# PHOTODIODE.net
KiCad netlist of a schematic drawn in Altium Designer
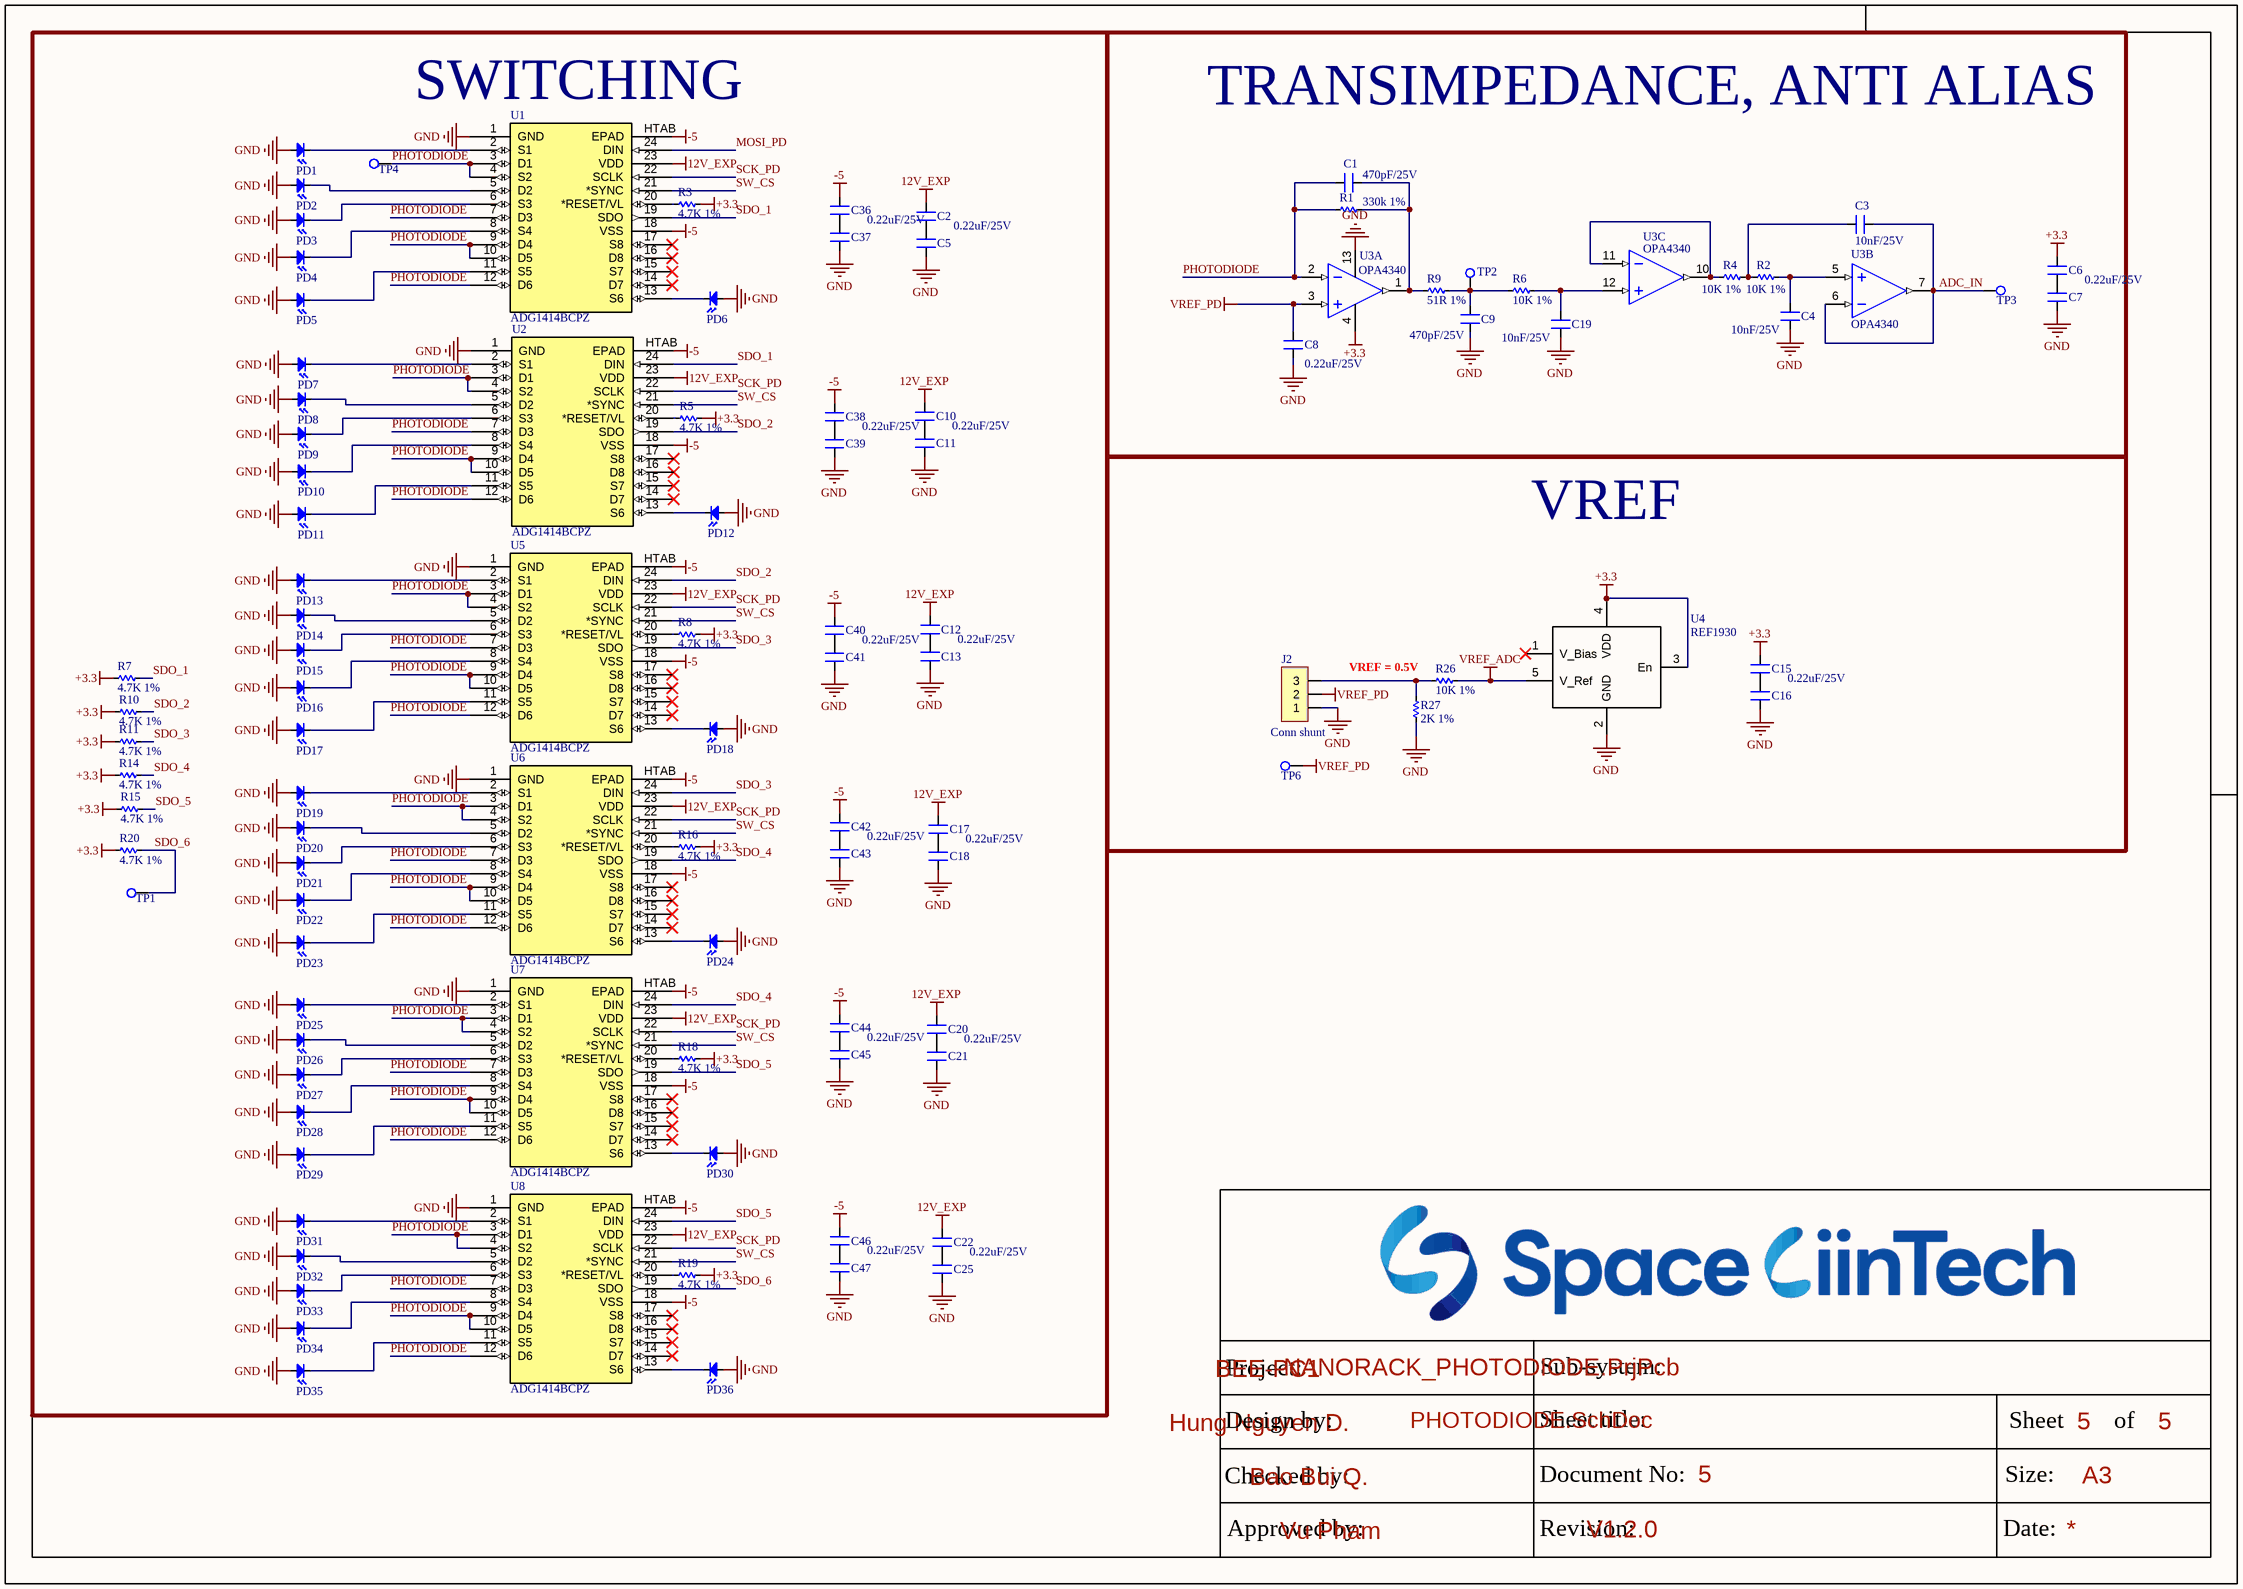
[diagram p0: PHOTODIODE.SchDoc]

(export (version "E")
  (design (tool "Eeschema 10.0.6"))
  (components
    (comp (ref "C1")
      (value "470pF/25V")
      (footprint "CN-SMD-0603")
      (description "0603")
      (libsource (lib "Capacitors") (part "CM"))
    )
    (comp (ref "C2")
      (value "0.22uF/25V")
      (footprint "CN-SMD-0603")
      (description "0603")
      (libsource (lib "Capacitors") (part "CM"))
    )
    (comp (ref "C3")
      (value "10nF/25V")
      (footprint "CN-SMD-0603")
      (description "0603")
      (libsource (lib "Capacitors") (part "CM"))
    )
    (comp (ref "C4")
      (value "10nF/25V")
      (footprint "CN-SMD-0603")
      (description "0603")
      (libsource (lib "Capacitors") (part "CM"))
    )
    (comp (ref "C5")
      (value "0.22uF/25V")
      (footprint "CN-SMD-0603")
      (description "0603")
      (libsource (lib "Capacitors") (part "CM"))
    )
    (comp (ref "C6")
      (value "0.22uF/25V")
      (footprint "CN-SMD-0603")
      (description "0603")
      (libsource (lib "Capacitors") (part "CM"))
    )
    (comp (ref "C7")
      (value "0.22uF/25V")
      (footprint "CN-SMD-0603")
      (description "0603")
      (libsource (lib "Capacitors") (part "CM"))
    )
    (comp (ref "C8")
      (value "0.22uF/25V")
      (footprint "CN-SMD-0603")
      (description "0603")
      (libsource (lib "Capacitors") (part "CM"))
    )
    (comp (ref "C9")
      (value "470pF/25V")
      (footprint "CN-SMD-0603")
      (description "0603")
      (libsource (lib "Capacitors") (part "CM"))
    )
    (comp (ref "C10")
      (value "0.22uF/25V")
      (footprint "CN-SMD-0603")
      (description "0603")
      (libsource (lib "Capacitors") (part "CM"))
    )
    (comp (ref "C11")
      (value "0.22uF/25V")
      (footprint "CN-SMD-0603")
      (description "0603")
      (libsource (lib "Capacitors") (part "CM"))
    )
    (comp (ref "C12")
      (value "0.22uF/25V")
      (footprint "CN-SMD-0603")
      (description "0603")
      (libsource (lib "Capacitors") (part "CM"))
    )
    (comp (ref "C13")
      (value "0.22uF/25V")
      (footprint "CN-SMD-0603")
      (description "0603")
      (libsource (lib "Capacitors") (part "CM"))
    )
    (comp (ref "C15")
      (value "0.22uF/25V")
      (footprint "CN-SMD-0603")
      (description "0603")
      (libsource (lib "Capacitors") (part "CM"))
    )
    (comp (ref "C16")
      (value "0.22uF/25V")
      (footprint "CN-SMD-0603")
      (description "0603")
      (libsource (lib "Capacitors") (part "CM"))
    )
    (comp (ref "C17")
      (value "0.22uF/25V")
      (footprint "CN-SMD-0603")
      (description "0603")
      (libsource (lib "Capacitors") (part "CM"))
    )
    (comp (ref "C18")
      (value "0.22uF/25V")
      (footprint "CN-SMD-0603")
      (description "0603")
      (libsource (lib "Capacitors") (part "CM"))
    )
    (comp (ref "C19")
      (value "10nF/25V")
      (footprint "CN-SMD-0603")
      (description "0603")
      (libsource (lib "Capacitors") (part "CM"))
    )
    (comp (ref "C20")
      (value "0.22uF/25V")
      (footprint "CN-SMD-0603")
      (description "0603")
      (libsource (lib "Capacitors") (part "CM"))
    )
    (comp (ref "C21")
      (value "0.22uF/25V")
      (footprint "CN-SMD-0603")
      (description "0603")
      (libsource (lib "Capacitors") (part "CM"))
    )
    (comp (ref "C22")
      (value "0.22uF/25V")
      (footprint "CN-SMD-0603")
      (description "0603")
      (libsource (lib "Capacitors") (part "CM"))
    )
    (comp (ref "C25")
      (value "0.22uF/25V")
      (footprint "CN-SMD-0603")
      (description "0603")
      (libsource (lib "Capacitors") (part "CM"))
    )
    (comp (ref "C36")
      (value "0.22uF/25V")
      (footprint "CN-SMD-0603")
      (description "0603")
      (libsource (lib "Capacitors") (part "CM"))
    )
    (comp (ref "C37")
      (value "0.22uF/25V")
      (footprint "CN-SMD-0603")
      (description "0603")
      (libsource (lib "Capacitors") (part "CM"))
    )
    (comp (ref "C38")
      (value "0.22uF/25V")
      (footprint "CN-SMD-0603")
      (description "0603")
      (libsource (lib "Capacitors") (part "CM"))
    )
    (comp (ref "C39")
      (value "0.22uF/25V")
      (footprint "CN-SMD-0603")
      (description "0603")
      (libsource (lib "Capacitors") (part "CM"))
    )
    (comp (ref "C40")
      (value "0.22uF/25V")
      (footprint "CN-SMD-0603")
      (description "0603")
      (libsource (lib "Capacitors") (part "CM"))
    )
    (comp (ref "C41")
      (value "0.22uF/25V")
      (footprint "CN-SMD-0603")
      (description "0603")
      (libsource (lib "Capacitors") (part "CM"))
    )
    (comp (ref "C42")
      (value "0.22uF/25V")
      (footprint "CN-SMD-0603")
      (description "0603")
      (libsource (lib "Capacitors") (part "CM"))
    )
    (comp (ref "C43")
      (value "0.22uF/25V")
      (footprint "CN-SMD-0603")
      (description "0603")
      (libsource (lib "Capacitors") (part "CM"))
    )
    (comp (ref "C44")
      (value "0.22uF/25V")
      (footprint "CN-SMD-0603")
      (description "0603")
      (libsource (lib "Capacitors") (part "CM"))
    )
    (comp (ref "C45")
      (value "0.22uF/25V")
      (footprint "CN-SMD-0603")
      (description "0603")
      (libsource (lib "Capacitors") (part "CM"))
    )
    (comp (ref "C46")
      (value "0.22uF/25V")
      (footprint "CN-SMD-0603")
      (description "0603")
      (libsource (lib "Capacitors") (part "CM"))
    )
    (comp (ref "C47")
      (value "0.22uF/25V")
      (footprint "CN-SMD-0603")
      (description "0603")
      (libsource (lib "Capacitors") (part "CM"))
    )
    (comp (ref "J2")
      (value "Conn shunt")
      (footprint "M50-3930342")
      (description "WR-PHD 2.54 mm Angled Socket Header")
      (fields
        (field (name "MANUFACTURER") "Würth Elektronik eiSos GmbH")
        (field (name "PARTNO") "613003143121")
        (field (name "CREATED BY") "Karrer Zheng")
      )
      (libsource (lib "Library") (part "JP3"))
    )
    (comp (ref "PD1")
      (value "Photodiode")
      (footprint "VEMD5080X01")
      (libsource (lib "Library_HUNG") (part "Photodiode"))
    )
    (comp (ref "PD2")
      (value "Photodiode")
      (footprint "VEMD5080X01")
      (libsource (lib "Library_HUNG") (part "Photodiode"))
    )
    (comp (ref "PD3")
      (value "Photodiode")
      (footprint "VEMD5080X01")
      (libsource (lib "Library_HUNG") (part "Photodiode"))
    )
    (comp (ref "PD4")
      (value "Photodiode")
      (footprint "VEMD5080X01")
      (libsource (lib "Library_HUNG") (part "Photodiode"))
    )
    (comp (ref "PD5")
      (value "Photodiode")
      (footprint "VEMD5080X01")
      (libsource (lib "Library_HUNG") (part "Photodiode"))
    )
    (comp (ref "PD6")
      (value "Photodiode")
      (footprint "VEMD5080X01")
      (libsource (lib "Library_HUNG") (part "Photodiode"))
    )
    (comp (ref "PD7")
      (value "Photodiode")
      (footprint "VEMD5080X01")
      (libsource (lib "Library_HUNG") (part "Photodiode"))
    )
    (comp (ref "PD8")
      (value "Photodiode")
      (footprint "VEMD5080X01")
      (libsource (lib "Library_HUNG") (part "Photodiode"))
    )
    (comp (ref "PD9")
      (value "Photodiode")
      (footprint "VEMD5080X01")
      (libsource (lib "Library_HUNG") (part "Photodiode"))
    )
    (comp (ref "PD10")
      (value "Photodiode")
      (footprint "VEMD5080X01")
      (libsource (lib "Library_HUNG") (part "Photodiode"))
    )
    (comp (ref "PD11")
      (value "Photodiode")
      (footprint "VEMD5080X01")
      (libsource (lib "Library_HUNG") (part "Photodiode"))
    )
    (comp (ref "PD12")
      (value "Photodiode")
      (footprint "VEMD5080X01")
      (libsource (lib "Library_HUNG") (part "Photodiode"))
    )
    (comp (ref "PD13")
      (value "Photodiode")
      (footprint "VEMD5080X01")
      (libsource (lib "Library_HUNG") (part "Photodiode"))
    )
    (comp (ref "PD14")
      (value "Photodiode")
      (footprint "VEMD5080X01")
      (libsource (lib "Library_HUNG") (part "Photodiode"))
    )
    (comp (ref "PD15")
      (value "Photodiode")
      (footprint "VEMD5080X01")
      (libsource (lib "Library_HUNG") (part "Photodiode"))
    )
    (comp (ref "PD16")
      (value "Photodiode")
      (footprint "VEMD5080X01")
      (libsource (lib "Library_HUNG") (part "Photodiode"))
    )
    (comp (ref "PD17")
      (value "Photodiode")
      (footprint "VEMD5080X01")
      (libsource (lib "Library_HUNG") (part "Photodiode"))
    )
    (comp (ref "PD18")
      (value "Photodiode")
      (footprint "VEMD5080X01")
      (libsource (lib "Library_HUNG") (part "Photodiode"))
    )
    (comp (ref "PD19")
      (value "Photodiode")
      (footprint "VEMD5080X01")
      (libsource (lib "Library_HUNG") (part "Photodiode"))
    )
    (comp (ref "PD20")
      (value "Photodiode")
      (footprint "VEMD5080X01")
      (libsource (lib "Library_HUNG") (part "Photodiode"))
    )
    (comp (ref "PD21")
      (value "Photodiode")
      (footprint "VEMD5080X01")
      (libsource (lib "Library_HUNG") (part "Photodiode"))
    )
    (comp (ref "PD22")
      (value "Photodiode")
      (footprint "VEMD5080X01")
      (libsource (lib "Library_HUNG") (part "Photodiode"))
    )
    (comp (ref "PD23")
      (value "Photodiode")
      (footprint "VEMD5080X01")
      (libsource (lib "Library_HUNG") (part "Photodiode"))
    )
    (comp (ref "PD24")
      (value "Photodiode")
      (footprint "VEMD5080X01")
      (libsource (lib "Library_HUNG") (part "Photodiode"))
    )
    (comp (ref "PD25")
      (value "Photodiode")
      (footprint "VEMD5080X01")
      (libsource (lib "Library_HUNG") (part "Photodiode"))
    )
    (comp (ref "PD26")
      (value "Photodiode")
      (footprint "VEMD5080X01")
      (libsource (lib "Library_HUNG") (part "Photodiode"))
    )
    (comp (ref "PD27")
      (value "Photodiode")
      (footprint "VEMD5080X01")
      (libsource (lib "Library_HUNG") (part "Photodiode"))
    )
    (comp (ref "PD28")
      (value "Photodiode")
      (footprint "VEMD5080X01")
      (libsource (lib "Library_HUNG") (part "Photodiode"))
    )
    (comp (ref "PD29")
      (value "Photodiode")
      (footprint "VEMD5080X01")
      (libsource (lib "Library_HUNG") (part "Photodiode"))
    )
    (comp (ref "PD30")
      (value "Photodiode")
      (footprint "VEMD5080X01")
      (libsource (lib "Library_HUNG") (part "Photodiode"))
    )
    (comp (ref "PD31")
      (value "Photodiode")
      (footprint "VEMD5080X01")
      (libsource (lib "Library_HUNG") (part "Photodiode"))
    )
    (comp (ref "PD32")
      (value "Photodiode")
      (footprint "VEMD5080X01")
      (libsource (lib "Library_HUNG") (part "Photodiode"))
    )
    (comp (ref "PD33")
      (value "Photodiode")
      (footprint "VEMD5080X01")
      (libsource (lib "Library_HUNG") (part "Photodiode"))
    )
    (comp (ref "PD34")
      (value "Photodiode")
      (footprint "VEMD5080X01")
      (libsource (lib "Library_HUNG") (part "Photodiode"))
    )
    (comp (ref "PD35")
      (value "Photodiode")
      (footprint "VEMD5080X01")
      (libsource (lib "Library_HUNG") (part "Photodiode"))
    )
    (comp (ref "PD36")
      (value "Photodiode")
      (footprint "VEMD5080X01")
      (libsource (lib "Library_HUNG") (part "Photodiode"))
    )
    (comp (ref "R1")
      (value "330k 1%")
      (footprint "RES-SMD-0603")
      (description "0603")
      (fields
        (field (name "MANUFACTURER") "Generic Components")
        (field (name "PUBLISHER") "Altium Hobart Technology Centre")
      )
      (libsource (lib "Library") (part "Res-SMD"))
    )
    (comp (ref "R2")
      (value "10K 1%")
      (footprint "RES-SMD-0603")
      (description "0603")
      (fields
        (field (name "MANUFACTURER") "Generic Components")
        (field (name "PUBLISHER") "Altium Hobart Technology Centre")
      )
      (libsource (lib "Library") (part "Res-SMD"))
    )
    (comp (ref "R3")
      (value "4.7K 1%")
      (footprint "RES-SMD-0603")
      (description "0603")
      (fields
        (field (name "MANUFACTURER") "Generic Components")
        (field (name "PUBLISHER") "Altium Hobart Technology Centre")
      )
      (libsource (lib "Library") (part "Res-SMD"))
    )
    (comp (ref "R4")
      (value "10K 1%")
      (footprint "RES-SMD-0603")
      (description "0603")
      (fields
        (field (name "MANUFACTURER") "Generic Components")
        (field (name "PUBLISHER") "Altium Hobart Technology Centre")
      )
      (libsource (lib "Library") (part "Res-SMD"))
    )
    (comp (ref "R5")
      (value "4.7K 1%")
      (footprint "RES-SMD-0603")
      (description "0603")
      (fields
        (field (name "MANUFACTURER") "Generic Components")
        (field (name "PUBLISHER") "Altium Hobart Technology Centre")
      )
      (libsource (lib "Library") (part "Res-SMD"))
    )
    (comp (ref "R6")
      (value "10K 1%")
      (footprint "RES-SMD-0603")
      (description "0603")
      (fields
        (field (name "MANUFACTURER") "Generic Components")
        (field (name "PUBLISHER") "Altium Hobart Technology Centre")
      )
      (libsource (lib "Library") (part "Res-SMD"))
    )
    (comp (ref "R7")
      (value "4.7K 1%")
      (footprint "RES-SMD-0603")
      (description "0603")
      (fields
        (field (name "MANUFACTURER") "Generic Components")
        (field (name "PUBLISHER") "Altium Hobart Technology Centre")
      )
      (libsource (lib "Library") (part "Res-SMD"))
    )
    (comp (ref "R8")
      (value "4.7K 1%")
      (footprint "RES-SMD-0603")
      (description "0603")
      (fields
        (field (name "MANUFACTURER") "Generic Components")
        (field (name "PUBLISHER") "Altium Hobart Technology Centre")
      )
      (libsource (lib "Library") (part "Res-SMD"))
    )
    (comp (ref "R9")
      (value "51R 1%")
      (footprint "RES-SMD-0603")
      (description "0603")
      (fields
        (field (name "MANUFACTURER") "Generic Components")
        (field (name "PUBLISHER") "Altium Hobart Technology Centre")
      )
      (libsource (lib "Library") (part "Res-SMD"))
    )
    (comp (ref "R10")
      (value "4.7K 1%")
      (footprint "RES-SMD-0603")
      (description "0603")
      (fields
        (field (name "MANUFACTURER") "Generic Components")
        (field (name "PUBLISHER") "Altium Hobart Technology Centre")
      )
      (libsource (lib "Library") (part "Res-SMD"))
    )
    (comp (ref "R11")
      (value "4.7K 1%")
      (footprint "RES-SMD-0603")
      (description "0603")
      (fields
        (field (name "MANUFACTURER") "Generic Components")
        (field (name "PUBLISHER") "Altium Hobart Technology Centre")
      )
      (libsource (lib "Library") (part "Res-SMD"))
    )
    (comp (ref "R14")
      (value "4.7K 1%")
      (footprint "RES-SMD-0603")
      (description "0603")
      (fields
        (field (name "MANUFACTURER") "Generic Components")
        (field (name "PUBLISHER") "Altium Hobart Technology Centre")
      )
      (libsource (lib "Library") (part "Res-SMD"))
    )
    (comp (ref "R15")
      (value "4.7K 1%")
      (footprint "RES-SMD-0603")
      (description "0603")
      (fields
        (field (name "MANUFACTURER") "Generic Components")
        (field (name "PUBLISHER") "Altium Hobart Technology Centre")
      )
      (libsource (lib "Library") (part "Res-SMD"))
    )
    (comp (ref "R16")
      (value "4.7K 1%")
      (footprint "RES-SMD-0603")
      (description "0603")
      (fields
        (field (name "MANUFACTURER") "Generic Components")
        (field (name "PUBLISHER") "Altium Hobart Technology Centre")
      )
      (libsource (lib "Library") (part "Res-SMD"))
    )
    (comp (ref "R18")
      (value "4.7K 1%")
      (footprint "RES-SMD-0603")
      (description "0603")
      (fields
        (field (name "MANUFACTURER") "Generic Components")
        (field (name "PUBLISHER") "Altium Hobart Technology Centre")
      )
      (libsource (lib "Library") (part "Res-SMD"))
    )
    (comp (ref "R19")
      (value "4.7K 1%")
      (footprint "RES-SMD-0603")
      (description "0603")
      (fields
        (field (name "MANUFACTURER") "Generic Components")
        (field (name "PUBLISHER") "Altium Hobart Technology Centre")
      )
      (libsource (lib "Library") (part "Res-SMD"))
    )
    (comp (ref "R20")
      (value "4.7K 1%")
      (footprint "RES-SMD-0603")
      (description "0603")
      (fields
        (field (name "MANUFACTURER") "Generic Components")
        (field (name "PUBLISHER") "Altium Hobart Technology Centre")
      )
      (libsource (lib "Library") (part "Res-SMD"))
    )
    (comp (ref "R26")
      (value "10K 1%")
      (footprint "RES-SMD-0603")
      (description "0603")
      (fields
        (field (name "MANUFACTURER") "Generic Components")
        (field (name "PUBLISHER") "Altium Hobart Technology Centre")
      )
      (libsource (lib "Library") (part "Res-SMD"))
    )
    (comp (ref "R27")
      (value "2K 1%")
      (footprint "RES-SMD-0603")
      (description "0603")
      (fields
        (field (name "MANUFACTURER") "Generic Components")
        (field (name "PUBLISHER") "Altium Hobart Technology Centre")
      )
      (libsource (lib "Library") (part "Res-SMD"))
    )
    (comp (ref "TP1")
      (value "Test_Point")
      (footprint "TESTPOINT")
      (libsource (lib "Library_HUNG") (part "Test_Point"))
    )
    (comp (ref "TP2")
      (value "Test_Point")
      (footprint "TESTPOINT")
      (libsource (lib "Library_HUNG") (part "Test_Point"))
    )
    (comp (ref "TP3")
      (value "Test_Point")
      (footprint "TESTPOINT")
      (libsource (lib "Library_HUNG") (part "Test_Point"))
    )
    (comp (ref "TP4")
      (value "Test_Point")
      (footprint "TESTPOINT")
      (libsource (lib "Library_HUNG") (part "Test_Point"))
    )
    (comp (ref "TP6")
      (value "Test_Point")
      (footprint "TESTPOINT")
      (libsource (lib "Library_HUNG") (part "Test_Point"))
    )
    (comp (ref "U1")
      (value "ADG1414BCPZ")
      (footprint "ADG1414BCPZ")
      (description "IC SW SPST-NOX8 11.5OHM 24LFCSP")
      (libsource (lib "Library_HUNG") (part "ADG1414"))
    )
    (comp (ref "U2")
      (value "ADG1414BCPZ")
      (footprint "ADG1414BCPZ")
      (description "IC SW SPST-NOX8 11.5OHM 24LFCSP")
      (libsource (lib "Library_HUNG") (part "ADG1414"))
    )
    (comp (ref "U3")
      (value "OPA4340")
      (footprint "SSOP16")
      (description "IC CMOS 4 CIRCUIT 16SSOP")
      (libsource (lib "Library") (part "OPA4340"))
    )
    (comp (ref "U4")
      (value "REF1930")
      (footprint "SOT23-5")
      (description "REF1941AIDDCT")
      (libsource (lib "Library") (part "REF19xx"))
    )
    (comp (ref "U5")
      (value "ADG1414BCPZ")
      (footprint "ADG1414BCPZ")
      (description "IC SW SPST-NOX8 11.5OHM 24LFCSP")
      (libsource (lib "Library_HUNG") (part "ADG1414"))
    )
    (comp (ref "U6")
      (value "ADG1414BCPZ")
      (footprint "ADG1414BCPZ")
      (description "IC SW SPST-NOX8 11.5OHM 24LFCSP")
      (libsource (lib "Library_HUNG") (part "ADG1414"))
    )
    (comp (ref "U7")
      (value "ADG1414BCPZ")
      (footprint "ADG1414BCPZ")
      (description "IC SW SPST-NOX8 11.5OHM 24LFCSP")
      (libsource (lib "Library_HUNG") (part "ADG1414"))
    )
    (comp (ref "U8")
      (value "ADG1414BCPZ")
      (footprint "ADG1414BCPZ")
      (description "IC SW SPST-NOX8 11.5OHM 24LFCSP")
      (libsource (lib "Library_HUNG") (part "ADG1414"))
    )
  )
  (nets
    (net (code "1") (name "+3.3") (class "Default")
      (node (ref "C15") (pin "2") (pinfunction "2_2") (pintype "passive"))
      (node (ref "C6") (pin "2") (pinfunction "2_2") (pintype "passive"))
      (node (ref "R10") (pin "2") (pinfunction "2_2") (pintype "passive"))
      (node (ref "R11") (pin "2") (pinfunction "2_2") (pintype "passive"))
      (node (ref "R14") (pin "2") (pinfunction "2_2") (pintype "passive"))
      (node (ref "R15") (pin "2") (pinfunction "2_2") (pintype "passive"))
      (node (ref "R16") (pin "2") (pinfunction "2_2") (pintype "passive"))
      (node (ref "R18") (pin "2") (pinfunction "2_2") (pintype "passive"))
      (node (ref "R19") (pin "2") (pinfunction "2_2") (pintype "passive"))
      (node (ref "R20") (pin "2") (pinfunction "2_2") (pintype "passive"))
      (node (ref "R3") (pin "2") (pinfunction "2_2") (pintype "passive"))
      (node (ref "R5") (pin "2") (pinfunction "2_2") (pintype "passive"))
      (node (ref "R7") (pin "2") (pinfunction "2_2") (pintype "passive"))
      (node (ref "R8") (pin "2") (pinfunction "2_2") (pintype "passive"))
      (node (ref "U3") (pin "4") (pinfunction "+V_4") (pintype "passive"))
      (node (ref "U4") (pin "3") (pinfunction "En_3") (pintype "passive"))
      (node (ref "U4") (pin "4") (pinfunction "VDD_4") (pintype "passive"))
    )
    (net (code "2") (name "-5") (class "Default")
      (node (ref "C36") (pin "2") (pinfunction "2_2") (pintype "passive"))
      (node (ref "C38") (pin "2") (pinfunction "2_2") (pintype "passive"))
      (node (ref "C40") (pin "2") (pinfunction "2_2") (pintype "passive"))
      (node (ref "C42") (pin "2") (pinfunction "2_2") (pintype "passive"))
      (node (ref "C44") (pin "2") (pinfunction "2_2") (pintype "passive"))
      (node (ref "C46") (pin "2") (pinfunction "2_2") (pintype "passive"))
      (node (ref "U1") (pin "18") (pinfunction "VSS_18") (pintype "power_in"))
      (node (ref "U1") (pin "HTAB") (pinfunction "EPAD_HTAB") (pintype "passive"))
      (node (ref "U2") (pin "18") (pinfunction "VSS_18") (pintype "power_in"))
      (node (ref "U2") (pin "HTAB") (pinfunction "EPAD_HTAB") (pintype "passive"))
      (node (ref "U5") (pin "18") (pinfunction "VSS_18") (pintype "power_in"))
      (node (ref "U5") (pin "HTAB") (pinfunction "EPAD_HTAB") (pintype "passive"))
      (node (ref "U6") (pin "18") (pinfunction "VSS_18") (pintype "power_in"))
      (node (ref "U6") (pin "HTAB") (pinfunction "EPAD_HTAB") (pintype "passive"))
      (node (ref "U7") (pin "18") (pinfunction "VSS_18") (pintype "power_in"))
      (node (ref "U7") (pin "HTAB") (pinfunction "EPAD_HTAB") (pintype "passive"))
      (node (ref "U8") (pin "18") (pinfunction "VSS_18") (pintype "power_in"))
      (node (ref "U8") (pin "HTAB") (pinfunction "EPAD_HTAB") (pintype "passive"))
    )
    (net (code "3") (name "/ADC_IN") (class "Default")
      (node (ref "C3") (pin "1") (pinfunction "1_1") (pintype "passive"))
      (node (ref "TP3") (pin "1") (pintype "power_in"))
      (node (ref "U3") (pin "6") (pinfunction "IN-_6") (pintype "input"))
      (node (ref "U3") (pin "7") (pinfunction "OUT_7") (pintype "output"))
    )
    (net (code "4") (name "/MOSI_PD") (class "Default")
      (node (ref "U1") (pin "24") (pinfunction "DIN_24") (pintype "input"))
    )
    (net (code "5") (name "/PHOTODIODE") (class "Default")
      (node (ref "C1") (pin "1") (pinfunction "1_1") (pintype "passive"))
      (node (ref "R1") (pin "1") (pinfunction "1_1") (pintype "passive"))
      (node (ref "TP4") (pin "1") (pintype "power_in"))
      (node (ref "U1") (pin "10") (pinfunction "D5_10") (pintype "bidirectional"))
      (node (ref "U1") (pin "12") (pinfunction "D6_12") (pintype "bidirectional"))
      (node (ref "U1") (pin "3") (pinfunction "D1_3") (pintype "bidirectional"))
      (node (ref "U1") (pin "4") (pinfunction "S2_4") (pintype "bidirectional"))
      (node (ref "U1") (pin "7") (pinfunction "D3_7") (pintype "bidirectional"))
      (node (ref "U1") (pin "9") (pinfunction "D4_9") (pintype "bidirectional"))
      (node (ref "U2") (pin "10") (pinfunction "D5_10") (pintype "bidirectional"))
      (node (ref "U2") (pin "12") (pinfunction "D6_12") (pintype "bidirectional"))
      (node (ref "U2") (pin "3") (pinfunction "D1_3") (pintype "bidirectional"))
      (node (ref "U2") (pin "4") (pinfunction "S2_4") (pintype "bidirectional"))
      (node (ref "U2") (pin "7") (pinfunction "D3_7") (pintype "bidirectional"))
      (node (ref "U2") (pin "9") (pinfunction "D4_9") (pintype "bidirectional"))
      (node (ref "U3") (pin "2") (pinfunction "IN-_2") (pintype "input"))
      (node (ref "U5") (pin "10") (pinfunction "D5_10") (pintype "bidirectional"))
      (node (ref "U5") (pin "12") (pinfunction "D6_12") (pintype "bidirectional"))
      (node (ref "U5") (pin "3") (pinfunction "D1_3") (pintype "bidirectional"))
      (node (ref "U5") (pin "4") (pinfunction "S2_4") (pintype "bidirectional"))
      (node (ref "U5") (pin "7") (pinfunction "D3_7") (pintype "bidirectional"))
      (node (ref "U5") (pin "9") (pinfunction "D4_9") (pintype "bidirectional"))
      (node (ref "U6") (pin "10") (pinfunction "D5_10") (pintype "bidirectional"))
      (node (ref "U6") (pin "12") (pinfunction "D6_12") (pintype "bidirectional"))
      (node (ref "U6") (pin "3") (pinfunction "D1_3") (pintype "bidirectional"))
      (node (ref "U6") (pin "4") (pinfunction "S2_4") (pintype "bidirectional"))
      (node (ref "U6") (pin "7") (pinfunction "D3_7") (pintype "bidirectional"))
      (node (ref "U6") (pin "9") (pinfunction "D4_9") (pintype "bidirectional"))
      (node (ref "U7") (pin "10") (pinfunction "D5_10") (pintype "bidirectional"))
      (node (ref "U7") (pin "12") (pinfunction "D6_12") (pintype "bidirectional"))
      (node (ref "U7") (pin "3") (pinfunction "D1_3") (pintype "bidirectional"))
      (node (ref "U7") (pin "4") (pinfunction "S2_4") (pintype "bidirectional"))
      (node (ref "U7") (pin "7") (pinfunction "D3_7") (pintype "bidirectional"))
      (node (ref "U7") (pin "9") (pinfunction "D4_9") (pintype "bidirectional"))
      (node (ref "U8") (pin "10") (pinfunction "D5_10") (pintype "bidirectional"))
      (node (ref "U8") (pin "12") (pinfunction "D6_12") (pintype "bidirectional"))
      (node (ref "U8") (pin "3") (pinfunction "D1_3") (pintype "bidirectional"))
      (node (ref "U8") (pin "4") (pinfunction "S2_4") (pintype "bidirectional"))
      (node (ref "U8") (pin "7") (pinfunction "D3_7") (pintype "bidirectional"))
      (node (ref "U8") (pin "9") (pinfunction "D4_9") (pintype "bidirectional"))
    )
    (net (code "6") (name "/SCK_PD") (class "Default")
      (node (ref "U1") (pin "22") (pinfunction "SCLK_22") (pintype "input"))
      (node (ref "U2") (pin "22") (pinfunction "SCLK_22") (pintype "input"))
      (node (ref "U5") (pin "22") (pinfunction "SCLK_22") (pintype "input"))
      (node (ref "U6") (pin "22") (pinfunction "SCLK_22") (pintype "input"))
      (node (ref "U7") (pin "22") (pinfunction "SCLK_22") (pintype "input"))
      (node (ref "U8") (pin "22") (pinfunction "SCLK_22") (pintype "input"))
    )
    (net (code "7") (name "/SDO_1") (class "Default")
      (node (ref "R7") (pin "1") (pinfunction "1_1") (pintype "passive"))
      (node (ref "U1") (pin "19") (pinfunction "SDO_19") (pintype "output"))
      (node (ref "U2") (pin "24") (pinfunction "DIN_24") (pintype "input"))
    )
    (net (code "8") (name "/SDO_2") (class "Default")
      (node (ref "R10") (pin "1") (pinfunction "1_1") (pintype "passive"))
      (node (ref "U2") (pin "19") (pinfunction "SDO_19") (pintype "output"))
      (node (ref "U5") (pin "24") (pinfunction "DIN_24") (pintype "input"))
    )
    (net (code "9") (name "/SDO_3") (class "Default")
      (node (ref "R11") (pin "1") (pinfunction "1_1") (pintype "passive"))
      (node (ref "U5") (pin "19") (pinfunction "SDO_19") (pintype "output"))
      (node (ref "U6") (pin "24") (pinfunction "DIN_24") (pintype "input"))
    )
    (net (code "10") (name "/SDO_4") (class "Default")
      (node (ref "R14") (pin "1") (pinfunction "1_1") (pintype "passive"))
      (node (ref "U6") (pin "19") (pinfunction "SDO_19") (pintype "output"))
      (node (ref "U7") (pin "24") (pinfunction "DIN_24") (pintype "input"))
    )
    (net (code "11") (name "/SDO_5") (class "Default")
      (node (ref "R15") (pin "1") (pinfunction "1_1") (pintype "passive"))
      (node (ref "U7") (pin "19") (pinfunction "SDO_19") (pintype "output"))
      (node (ref "U8") (pin "24") (pinfunction "DIN_24") (pintype "input"))
    )
    (net (code "12") (name "/SDO_6") (class "Default")
      (node (ref "R20") (pin "1") (pinfunction "1_1") (pintype "passive"))
      (node (ref "TP1") (pin "1") (pintype "power_in"))
      (node (ref "U8") (pin "19") (pinfunction "SDO_19") (pintype "output"))
    )
    (net (code "13") (name "/SW_CS") (class "Default")
      (node (ref "U1") (pin "21") (pinfunction "*SYNC_21") (pintype "input"))
      (node (ref "U2") (pin "21") (pinfunction "*SYNC_21") (pintype "input"))
      (node (ref "U5") (pin "21") (pinfunction "*SYNC_21") (pintype "input"))
      (node (ref "U6") (pin "21") (pinfunction "*SYNC_21") (pintype "input"))
      (node (ref "U7") (pin "21") (pinfunction "*SYNC_21") (pintype "input"))
      (node (ref "U8") (pin "21") (pinfunction "*SYNC_21") (pintype "input"))
    )
    (net (code "14") (name "12V_EXP") (class "Default")
      (node (ref "C10") (pin "2") (pinfunction "2_2") (pintype "passive"))
      (node (ref "C12") (pin "2") (pinfunction "2_2") (pintype "passive"))
      (node (ref "C17") (pin "2") (pinfunction "2_2") (pintype "passive"))
      (node (ref "C2") (pin "2") (pinfunction "2_2") (pintype "passive"))
      (node (ref "C20") (pin "2") (pinfunction "2_2") (pintype "passive"))
      (node (ref "C22") (pin "2") (pinfunction "2_2") (pintype "passive"))
      (node (ref "U1") (pin "23") (pinfunction "VDD_23") (pintype "power_in"))
      (node (ref "U2") (pin "23") (pinfunction "VDD_23") (pintype "power_in"))
      (node (ref "U5") (pin "23") (pinfunction "VDD_23") (pintype "power_in"))
      (node (ref "U6") (pin "23") (pinfunction "VDD_23") (pintype "power_in"))
      (node (ref "U7") (pin "23") (pinfunction "VDD_23") (pintype "power_in"))
      (node (ref "U8") (pin "23") (pinfunction "VDD_23") (pintype "power_in"))
    )
    (net (code "15") (name "GND") (class "Default")
      (node (ref "C11") (pin "1") (pinfunction "1_1") (pintype "passive"))
      (node (ref "C13") (pin "1") (pinfunction "1_1") (pintype "passive"))
      (node (ref "C16") (pin "1") (pinfunction "1_1") (pintype "passive"))
      (node (ref "C18") (pin "1") (pinfunction "1_1") (pintype "passive"))
      (node (ref "C19") (pin "1") (pinfunction "1_1") (pintype "passive"))
      (node (ref "C21") (pin "1") (pinfunction "1_1") (pintype "passive"))
      (node (ref "C25") (pin "1") (pinfunction "1_1") (pintype "passive"))
      (node (ref "C37") (pin "1") (pinfunction "1_1") (pintype "passive"))
      (node (ref "C39") (pin "1") (pinfunction "1_1") (pintype "passive"))
      (node (ref "C4") (pin "1") (pinfunction "1_1") (pintype "passive"))
      (node (ref "C41") (pin "1") (pinfunction "1_1") (pintype "passive"))
      (node (ref "C43") (pin "1") (pinfunction "1_1") (pintype "passive"))
      (node (ref "C45") (pin "1") (pinfunction "1_1") (pintype "passive"))
      (node (ref "C47") (pin "1") (pinfunction "1_1") (pintype "passive"))
      (node (ref "C5") (pin "1") (pinfunction "1_1") (pintype "passive"))
      (node (ref "C7") (pin "1") (pinfunction "1_1") (pintype "passive"))
      (node (ref "C8") (pin "1") (pinfunction "1_1") (pintype "passive"))
      (node (ref "C9") (pin "1") (pinfunction "1_1") (pintype "passive"))
      (node (ref "J2") (pin "1") (pinfunction "1_1") (pintype "passive"))
      (node (ref "PD1") (pin "1") (pinfunction "A_1") (pintype "passive"))
      (node (ref "PD10") (pin "1") (pinfunction "A_1") (pintype "passive"))
      (node (ref "PD11") (pin "1") (pinfunction "A_1") (pintype "passive"))
      (node (ref "PD12") (pin "1") (pinfunction "A_1") (pintype "passive"))
      (node (ref "PD13") (pin "1") (pinfunction "A_1") (pintype "passive"))
      (node (ref "PD14") (pin "1") (pinfunction "A_1") (pintype "passive"))
      (node (ref "PD15") (pin "1") (pinfunction "A_1") (pintype "passive"))
      (node (ref "PD16") (pin "1") (pinfunction "A_1") (pintype "passive"))
      (node (ref "PD17") (pin "1") (pinfunction "A_1") (pintype "passive"))
      (node (ref "PD18") (pin "1") (pinfunction "A_1") (pintype "passive"))
      (node (ref "PD19") (pin "1") (pinfunction "A_1") (pintype "passive"))
      (node (ref "PD2") (pin "1") (pinfunction "A_1") (pintype "passive"))
      (node (ref "PD20") (pin "1") (pinfunction "A_1") (pintype "passive"))
      (node (ref "PD21") (pin "1") (pinfunction "A_1") (pintype "passive"))
      (node (ref "PD22") (pin "1") (pinfunction "A_1") (pintype "passive"))
      (node (ref "PD23") (pin "1") (pinfunction "A_1") (pintype "passive"))
      (node (ref "PD24") (pin "1") (pinfunction "A_1") (pintype "passive"))
      (node (ref "PD25") (pin "1") (pinfunction "A_1") (pintype "passive"))
      (node (ref "PD26") (pin "1") (pinfunction "A_1") (pintype "passive"))
      (node (ref "PD27") (pin "1") (pinfunction "A_1") (pintype "passive"))
      (node (ref "PD28") (pin "1") (pinfunction "A_1") (pintype "passive"))
      (node (ref "PD29") (pin "1") (pinfunction "A_1") (pintype "passive"))
      (node (ref "PD3") (pin "1") (pinfunction "A_1") (pintype "passive"))
      (node (ref "PD30") (pin "1") (pinfunction "A_1") (pintype "passive"))
      (node (ref "PD31") (pin "1") (pinfunction "A_1") (pintype "passive"))
      (node (ref "PD32") (pin "1") (pinfunction "A_1") (pintype "passive"))
      (node (ref "PD33") (pin "1") (pinfunction "A_1") (pintype "passive"))
      (node (ref "PD34") (pin "1") (pinfunction "A_1") (pintype "passive"))
      (node (ref "PD35") (pin "1") (pinfunction "A_1") (pintype "passive"))
      (node (ref "PD36") (pin "1") (pinfunction "A_1") (pintype "passive"))
      (node (ref "PD4") (pin "1") (pinfunction "A_1") (pintype "passive"))
      (node (ref "PD5") (pin "1") (pinfunction "A_1") (pintype "passive"))
      (node (ref "PD6") (pin "1") (pinfunction "A_1") (pintype "passive"))
      (node (ref "PD7") (pin "1") (pinfunction "A_1") (pintype "passive"))
      (node (ref "PD8") (pin "1") (pinfunction "A_1") (pintype "passive"))
      (node (ref "PD9") (pin "1") (pinfunction "A_1") (pintype "passive"))
      (node (ref "R27") (pin "1") (pinfunction "1_1") (pintype "passive"))
      (node (ref "U1") (pin "1") (pinfunction "GND_1") (pintype "power_in"))
      (node (ref "U2") (pin "1") (pinfunction "GND_1") (pintype "power_in"))
      (node (ref "U3") (pin "13") (pinfunction "-V_13") (pintype "passive"))
      (node (ref "U4") (pin "2") (pinfunction "GND_2") (pintype "passive"))
      (node (ref "U5") (pin "1") (pinfunction "GND_1") (pintype "power_in"))
      (node (ref "U6") (pin "1") (pinfunction "GND_1") (pintype "power_in"))
      (node (ref "U7") (pin "1") (pinfunction "GND_1") (pintype "power_in"))
      (node (ref "U8") (pin "1") (pinfunction "GND_1") (pintype "power_in"))
    )
    (net (code "16") (name "Net-(C2-Pad1)") (class "Default")
      (node (ref "C2") (pin "1") (pinfunction "1_1") (pintype "passive"))
      (node (ref "C5") (pin "2") (pinfunction "2_2") (pintype "passive"))
    )
    (net (code "17") (name "Net-(C3-Pad2)") (class "Default")
      (node (ref "C3") (pin "2") (pinfunction "2_2") (pintype "passive"))
      (node (ref "R2") (pin "1") (pinfunction "1_1") (pintype "passive"))
      (node (ref "R4") (pin "2") (pinfunction "2_2") (pintype "passive"))
    )
    (net (code "18") (name "Net-(C6-Pad1)") (class "Default")
      (node (ref "C6") (pin "1") (pinfunction "1_1") (pintype "passive"))
      (node (ref "C7") (pin "2") (pinfunction "2_2") (pintype "passive"))
    )
    (net (code "19") (name "Net-(C9-Pad2)") (class "Default")
      (node (ref "C9") (pin "2") (pinfunction "2_2") (pintype "passive"))
      (node (ref "R6") (pin "1") (pinfunction "1_1") (pintype "passive"))
      (node (ref "R9") (pin "2") (pinfunction "2_2") (pintype "passive"))
      (node (ref "TP2") (pin "1") (pintype "power_in"))
    )
    (net (code "20") (name "Net-(C10-Pad1)") (class "Default")
      (node (ref "C10") (pin "1") (pinfunction "1_1") (pintype "passive"))
      (node (ref "C11") (pin "2") (pinfunction "2_2") (pintype "passive"))
    )
    (net (code "21") (name "Net-(C12-Pad1)") (class "Default")
      (node (ref "C12") (pin "1") (pinfunction "1_1") (pintype "passive"))
      (node (ref "C13") (pin "2") (pinfunction "2_2") (pintype "passive"))
    )
    (net (code "22") (name "Net-(C15-Pad1)") (class "Default")
      (node (ref "C15") (pin "1") (pinfunction "1_1") (pintype "passive"))
      (node (ref "C16") (pin "2") (pinfunction "2_2") (pintype "passive"))
    )
    (net (code "23") (name "Net-(C17-Pad1)") (class "Default")
      (node (ref "C17") (pin "1") (pinfunction "1_1") (pintype "passive"))
      (node (ref "C18") (pin "2") (pinfunction "2_2") (pintype "passive"))
    )
    (net (code "24") (name "Net-(C20-Pad1)") (class "Default")
      (node (ref "C20") (pin "1") (pinfunction "1_1") (pintype "passive"))
      (node (ref "C21") (pin "2") (pinfunction "2_2") (pintype "passive"))
    )
    (net (code "25") (name "Net-(C22-Pad1)") (class "Default")
      (node (ref "C22") (pin "1") (pinfunction "1_1") (pintype "passive"))
      (node (ref "C25") (pin "2") (pinfunction "2_2") (pintype "passive"))
    )
    (net (code "26") (name "Net-(C36-Pad1)") (class "Default")
      (node (ref "C36") (pin "1") (pinfunction "1_1") (pintype "passive"))
      (node (ref "C37") (pin "2") (pinfunction "2_2") (pintype "passive"))
    )
    (net (code "27") (name "Net-(C38-Pad1)") (class "Default")
      (node (ref "C38") (pin "1") (pinfunction "1_1") (pintype "passive"))
      (node (ref "C39") (pin "2") (pinfunction "2_2") (pintype "passive"))
    )
    (net (code "28") (name "Net-(C40-Pad1)") (class "Default")
      (node (ref "C40") (pin "1") (pinfunction "1_1") (pintype "passive"))
      (node (ref "C41") (pin "2") (pinfunction "2_2") (pintype "passive"))
    )
    (net (code "29") (name "Net-(C42-Pad1)") (class "Default")
      (node (ref "C42") (pin "1") (pinfunction "1_1") (pintype "passive"))
      (node (ref "C43") (pin "2") (pinfunction "2_2") (pintype "passive"))
    )
    (net (code "30") (name "Net-(C44-Pad1)") (class "Default")
      (node (ref "C44") (pin "1") (pinfunction "1_1") (pintype "passive"))
      (node (ref "C45") (pin "2") (pinfunction "2_2") (pintype "passive"))
    )
    (net (code "31") (name "Net-(C46-Pad1)") (class "Default")
      (node (ref "C46") (pin "1") (pinfunction "1_1") (pintype "passive"))
      (node (ref "C47") (pin "2") (pinfunction "2_2") (pintype "passive"))
    )
    (net (code "32") (name "Net-(J2-Pad3)") (class "Default")
      (node (ref "J2") (pin "3") (pinfunction "3_3") (pintype "passive"))
      (node (ref "R26") (pin "2") (pinfunction "2_2") (pintype "passive"))
      (node (ref "R27") (pin "2") (pinfunction "2_2") (pintype "passive"))
    )
    (net (code "33") (name "Net-(PD1-K)") (class "Default")
      (node (ref "PD1") (pin "2") (pinfunction "K_2") (pintype "passive"))
      (node (ref "U1") (pin "2") (pinfunction "S1_2") (pintype "bidirectional"))
    )
    (net (code "34") (name "Net-(PD2-K)") (class "Default")
      (node (ref "PD2") (pin "2") (pinfunction "K_2") (pintype "passive"))
      (node (ref "U1") (pin "5") (pinfunction "D2_5") (pintype "bidirectional"))
    )
    (net (code "35") (name "Net-(PD3-K)") (class "Default")
      (node (ref "PD3") (pin "2") (pinfunction "K_2") (pintype "passive"))
      (node (ref "U1") (pin "6") (pinfunction "S3_6") (pintype "bidirectional"))
    )
    (net (code "36") (name "Net-(PD4-K)") (class "Default")
      (node (ref "PD4") (pin "2") (pinfunction "K_2") (pintype "passive"))
      (node (ref "U1") (pin "8") (pinfunction "S4_8") (pintype "bidirectional"))
    )
    (net (code "37") (name "Net-(PD5-K)") (class "Default")
      (node (ref "PD5") (pin "2") (pinfunction "K_2") (pintype "passive"))
      (node (ref "U1") (pin "11") (pinfunction "S5_11") (pintype "bidirectional"))
    )
    (net (code "38") (name "Net-(PD6-K)") (class "Default")
      (node (ref "PD6") (pin "2") (pinfunction "K_2") (pintype "passive"))
      (node (ref "U1") (pin "13") (pinfunction "S6_13") (pintype "bidirectional"))
    )
    (net (code "39") (name "Net-(PD7-K)") (class "Default")
      (node (ref "PD7") (pin "2") (pinfunction "K_2") (pintype "passive"))
      (node (ref "U2") (pin "2") (pinfunction "S1_2") (pintype "bidirectional"))
    )
    (net (code "40") (name "Net-(PD8-K)") (class "Default")
      (node (ref "PD8") (pin "2") (pinfunction "K_2") (pintype "passive"))
      (node (ref "U2") (pin "5") (pinfunction "D2_5") (pintype "bidirectional"))
    )
    (net (code "41") (name "Net-(PD9-K)") (class "Default")
      (node (ref "PD9") (pin "2") (pinfunction "K_2") (pintype "passive"))
      (node (ref "U2") (pin "6") (pinfunction "S3_6") (pintype "bidirectional"))
    )
    (net (code "42") (name "Net-(PD10-K)") (class "Default")
      (node (ref "PD10") (pin "2") (pinfunction "K_2") (pintype "passive"))
      (node (ref "U2") (pin "8") (pinfunction "S4_8") (pintype "bidirectional"))
    )
    (net (code "43") (name "Net-(PD11-K)") (class "Default")
      (node (ref "PD11") (pin "2") (pinfunction "K_2") (pintype "passive"))
      (node (ref "U2") (pin "11") (pinfunction "S5_11") (pintype "bidirectional"))
    )
    (net (code "44") (name "Net-(PD12-K)") (class "Default")
      (node (ref "PD12") (pin "2") (pinfunction "K_2") (pintype "passive"))
      (node (ref "U2") (pin "13") (pinfunction "S6_13") (pintype "bidirectional"))
    )
    (net (code "45") (name "Net-(PD13-K)") (class "Default")
      (node (ref "PD13") (pin "2") (pinfunction "K_2") (pintype "passive"))
      (node (ref "U5") (pin "2") (pinfunction "S1_2") (pintype "bidirectional"))
    )
    (net (code "46") (name "Net-(PD14-K)") (class "Default")
      (node (ref "PD14") (pin "2") (pinfunction "K_2") (pintype "passive"))
      (node (ref "U5") (pin "5") (pinfunction "D2_5") (pintype "bidirectional"))
    )
    (net (code "47") (name "Net-(PD15-K)") (class "Default")
      (node (ref "PD15") (pin "2") (pinfunction "K_2") (pintype "passive"))
      (node (ref "U5") (pin "6") (pinfunction "S3_6") (pintype "bidirectional"))
    )
    (net (code "48") (name "Net-(PD16-K)") (class "Default")
      (node (ref "PD16") (pin "2") (pinfunction "K_2") (pintype "passive"))
      (node (ref "U5") (pin "8") (pinfunction "S4_8") (pintype "bidirectional"))
    )
    (net (code "49") (name "Net-(PD17-K)") (class "Default")
      (node (ref "PD17") (pin "2") (pinfunction "K_2") (pintype "passive"))
      (node (ref "U5") (pin "11") (pinfunction "S5_11") (pintype "bidirectional"))
    )
    (net (code "50") (name "Net-(PD18-K)") (class "Default")
      (node (ref "PD18") (pin "2") (pinfunction "K_2") (pintype "passive"))
      (node (ref "U5") (pin "13") (pinfunction "S6_13") (pintype "bidirectional"))
    )
    (net (code "51") (name "Net-(PD19-K)") (class "Default")
      (node (ref "PD19") (pin "2") (pinfunction "K_2") (pintype "passive"))
      (node (ref "U6") (pin "2") (pinfunction "S1_2") (pintype "bidirectional"))
    )
    (net (code "52") (name "Net-(PD20-K)") (class "Default")
      (node (ref "PD20") (pin "2") (pinfunction "K_2") (pintype "passive"))
      (node (ref "U6") (pin "5") (pinfunction "D2_5") (pintype "bidirectional"))
    )
    (net (code "53") (name "Net-(PD21-K)") (class "Default")
      (node (ref "PD21") (pin "2") (pinfunction "K_2") (pintype "passive"))
      (node (ref "U6") (pin "6") (pinfunction "S3_6") (pintype "bidirectional"))
    )
    (net (code "54") (name "Net-(PD22-K)") (class "Default")
      (node (ref "PD22") (pin "2") (pinfunction "K_2") (pintype "passive"))
      (node (ref "U6") (pin "8") (pinfunction "S4_8") (pintype "bidirectional"))
    )
    (net (code "55") (name "Net-(PD23-K)") (class "Default")
      (node (ref "PD23") (pin "2") (pinfunction "K_2") (pintype "passive"))
      (node (ref "U6") (pin "11") (pinfunction "S5_11") (pintype "bidirectional"))
    )
    (net (code "56") (name "Net-(PD24-K)") (class "Default")
      (node (ref "PD24") (pin "2") (pinfunction "K_2") (pintype "passive"))
      (node (ref "U6") (pin "13") (pinfunction "S6_13") (pintype "bidirectional"))
    )
    (net (code "57") (name "Net-(PD25-K)") (class "Default")
      (node (ref "PD25") (pin "2") (pinfunction "K_2") (pintype "passive"))
      (node (ref "U7") (pin "2") (pinfunction "S1_2") (pintype "bidirectional"))
    )
    (net (code "58") (name "Net-(PD26-K)") (class "Default")
      (node (ref "PD26") (pin "2") (pinfunction "K_2") (pintype "passive"))
      (node (ref "U7") (pin "5") (pinfunction "D2_5") (pintype "bidirectional"))
    )
    (net (code "59") (name "Net-(PD27-K)") (class "Default")
      (node (ref "PD27") (pin "2") (pinfunction "K_2") (pintype "passive"))
      (node (ref "U7") (pin "6") (pinfunction "S3_6") (pintype "bidirectional"))
    )
    (net (code "60") (name "Net-(PD28-K)") (class "Default")
      (node (ref "PD28") (pin "2") (pinfunction "K_2") (pintype "passive"))
      (node (ref "U7") (pin "8") (pinfunction "S4_8") (pintype "bidirectional"))
    )
    (net (code "61") (name "Net-(PD29-K)") (class "Default")
      (node (ref "PD29") (pin "2") (pinfunction "K_2") (pintype "passive"))
      (node (ref "U7") (pin "11") (pinfunction "S5_11") (pintype "bidirectional"))
    )
    (net (code "62") (name "Net-(PD30-K)") (class "Default")
      (node (ref "PD30") (pin "2") (pinfunction "K_2") (pintype "passive"))
      (node (ref "U7") (pin "13") (pinfunction "S6_13") (pintype "bidirectional"))
    )
    (net (code "63") (name "Net-(PD31-K)") (class "Default")
      (node (ref "PD31") (pin "2") (pinfunction "K_2") (pintype "passive"))
      (node (ref "U8") (pin "2") (pinfunction "S1_2") (pintype "bidirectional"))
    )
    (net (code "64") (name "Net-(PD32-K)") (class "Default")
      (node (ref "PD32") (pin "2") (pinfunction "K_2") (pintype "passive"))
      (node (ref "U8") (pin "5") (pinfunction "D2_5") (pintype "bidirectional"))
    )
    (net (code "65") (name "Net-(PD33-K)") (class "Default")
      (node (ref "PD33") (pin "2") (pinfunction "K_2") (pintype "passive"))
      (node (ref "U8") (pin "6") (pinfunction "S3_6") (pintype "bidirectional"))
    )
    (net (code "66") (name "Net-(PD34-K)") (class "Default")
      (node (ref "PD34") (pin "2") (pinfunction "K_2") (pintype "passive"))
      (node (ref "U8") (pin "8") (pinfunction "S4_8") (pintype "bidirectional"))
    )
    (net (code "67") (name "Net-(PD35-K)") (class "Default")
      (node (ref "PD35") (pin "2") (pinfunction "K_2") (pintype "passive"))
      (node (ref "U8") (pin "11") (pinfunction "S5_11") (pintype "bidirectional"))
    )
    (net (code "68") (name "Net-(PD36-K)") (class "Default")
      (node (ref "PD36") (pin "2") (pinfunction "K_2") (pintype "passive"))
      (node (ref "U8") (pin "13") (pinfunction "S6_13") (pintype "bidirectional"))
    )
    (net (code "69") (name "Net-(U1-*RESET{slash}VL)") (class "Default")
      (node (ref "R3") (pin "1") (pinfunction "1_1") (pintype "passive"))
      (node (ref "U1") (pin "20") (pinfunction "*RESET/VL_20") (pintype "bidirectional"))
    )
    (net (code "70") (name "Net-(U2-*RESET{slash}VL)") (class "Default")
      (node (ref "R5") (pin "1") (pinfunction "1_1") (pintype "passive"))
      (node (ref "U2") (pin "20") (pinfunction "*RESET/VL_20") (pintype "bidirectional"))
    )
    (net (code "71") (name "Net-(U3A-OUT)") (class "Default")
      (node (ref "C1") (pin "2") (pinfunction "2_2") (pintype "passive"))
      (node (ref "R1") (pin "2") (pinfunction "2_2") (pintype "passive"))
      (node (ref "R9") (pin "1") (pinfunction "1_1") (pintype "passive"))
      (node (ref "U3") (pin "1") (pinfunction "OUT_1") (pintype "output"))
    )
    (net (code "72") (name "Net-(U3B-IN+)") (class "Default")
      (node (ref "C4") (pin "2") (pinfunction "2_2") (pintype "passive"))
      (node (ref "R2") (pin "2") (pinfunction "2_2") (pintype "passive"))
      (node (ref "U3") (pin "5") (pinfunction "IN+_5") (pintype "input"))
    )
    (net (code "73") (name "Net-(U3C-IN+)") (class "Default")
      (node (ref "C19") (pin "2") (pinfunction "2_2") (pintype "passive"))
      (node (ref "R6") (pin "2") (pinfunction "2_2") (pintype "passive"))
      (node (ref "U3") (pin "12") (pinfunction "IN+_12") (pintype "input"))
    )
    (net (code "74") (name "Net-(U3C-IN-)") (class "Default")
      (node (ref "R4") (pin "1") (pinfunction "1_1") (pintype "passive"))
      (node (ref "U3") (pin "10") (pinfunction "OUT_10") (pintype "output"))
      (node (ref "U3") (pin "11") (pinfunction "IN-_11") (pintype "input"))
    )
    (net (code "75") (name "Net-(U5-*RESET{slash}VL)") (class "Default")
      (node (ref "R8") (pin "1") (pinfunction "1_1") (pintype "passive"))
      (node (ref "U5") (pin "20") (pinfunction "*RESET/VL_20") (pintype "bidirectional"))
    )
    (net (code "76") (name "Net-(U6-*RESET{slash}VL)") (class "Default")
      (node (ref "R16") (pin "1") (pinfunction "1_1") (pintype "passive"))
      (node (ref "U6") (pin "20") (pinfunction "*RESET/VL_20") (pintype "bidirectional"))
    )
    (net (code "77") (name "Net-(U7-*RESET{slash}VL)") (class "Default")
      (node (ref "R18") (pin "1") (pinfunction "1_1") (pintype "passive"))
      (node (ref "U7") (pin "20") (pinfunction "*RESET/VL_20") (pintype "bidirectional"))
    )
    (net (code "78") (name "Net-(U8-*RESET{slash}VL)") (class "Default")
      (node (ref "R19") (pin "1") (pinfunction "1_1") (pintype "passive"))
      (node (ref "U8") (pin "20") (pinfunction "*RESET/VL_20") (pintype "bidirectional"))
    )
    (net (code "79") (name "VREF_ADC") (class "Default")
      (node (ref "R26") (pin "1") (pinfunction "1_1") (pintype "passive"))
      (node (ref "U4") (pin "5") (pinfunction "V_Ref_5") (pintype "passive"))
    )
    (net (code "80") (name "VREF_PD") (class "Default")
      (node (ref "C8") (pin "2") (pinfunction "2_2") (pintype "passive"))
      (node (ref "J2") (pin "2") (pinfunction "2_2") (pintype "passive"))
      (node (ref "TP6") (pin "1") (pintype "power_in"))
      (node (ref "U3") (pin "3") (pinfunction "IN+_3") (pintype "input"))
    )
    (net (code "81") (name "unconnected-(U1-D7-Pad14)") (class "Default")
      (node (ref "U1") (pin "14") (pinfunction "D7_14") (pintype "bidirectional+no_connect"))
    )
    (net (code "82") (name "unconnected-(U1-D8-Pad16)") (class "Default")
      (node (ref "U1") (pin "16") (pinfunction "D8_16") (pintype "bidirectional+no_connect"))
    )
    (net (code "83") (name "unconnected-(U1-S7-Pad15)") (class "Default")
      (node (ref "U1") (pin "15") (pinfunction "S7_15") (pintype "bidirectional+no_connect"))
    )
    (net (code "84") (name "unconnected-(U1-S8-Pad17)") (class "Default")
      (node (ref "U1") (pin "17") (pinfunction "S8_17") (pintype "bidirectional+no_connect"))
    )
    (net (code "85") (name "unconnected-(U2-D7-Pad14)") (class "Default")
      (node (ref "U2") (pin "14") (pinfunction "D7_14") (pintype "bidirectional+no_connect"))
    )
    (net (code "86") (name "unconnected-(U2-D8-Pad16)") (class "Default")
      (node (ref "U2") (pin "16") (pinfunction "D8_16") (pintype "bidirectional+no_connect"))
    )
    (net (code "87") (name "unconnected-(U2-S7-Pad15)") (class "Default")
      (node (ref "U2") (pin "15") (pinfunction "S7_15") (pintype "bidirectional+no_connect"))
    )
    (net (code "88") (name "unconnected-(U2-S8-Pad17)") (class "Default")
      (node (ref "U2") (pin "17") (pinfunction "S8_17") (pintype "bidirectional+no_connect"))
    )
    (net (code "89") (name "unconnected-(U4-V_Bias-Pad1)") (class "Default")
      (node (ref "U4") (pin "1") (pinfunction "V_Bias_1") (pintype "passive+no_connect"))
    )
    (net (code "90") (name "unconnected-(U5-D7-Pad14)") (class "Default")
      (node (ref "U5") (pin "14") (pinfunction "D7_14") (pintype "bidirectional+no_connect"))
    )
    (net (code "91") (name "unconnected-(U5-D8-Pad16)") (class "Default")
      (node (ref "U5") (pin "16") (pinfunction "D8_16") (pintype "bidirectional+no_connect"))
    )
    (net (code "92") (name "unconnected-(U5-S7-Pad15)") (class "Default")
      (node (ref "U5") (pin "15") (pinfunction "S7_15") (pintype "bidirectional+no_connect"))
    )
    (net (code "93") (name "unconnected-(U5-S8-Pad17)") (class "Default")
      (node (ref "U5") (pin "17") (pinfunction "S8_17") (pintype "bidirectional+no_connect"))
    )
    (net (code "94") (name "unconnected-(U6-D7-Pad14)") (class "Default")
      (node (ref "U6") (pin "14") (pinfunction "D7_14") (pintype "bidirectional+no_connect"))
    )
    (net (code "95") (name "unconnected-(U6-D8-Pad16)") (class "Default")
      (node (ref "U6") (pin "16") (pinfunction "D8_16") (pintype "bidirectional+no_connect"))
    )
    (net (code "96") (name "unconnected-(U6-S7-Pad15)") (class "Default")
      (node (ref "U6") (pin "15") (pinfunction "S7_15") (pintype "bidirectional+no_connect"))
    )
    (net (code "97") (name "unconnected-(U6-S8-Pad17)") (class "Default")
      (node (ref "U6") (pin "17") (pinfunction "S8_17") (pintype "bidirectional+no_connect"))
    )
    (net (code "98") (name "unconnected-(U7-D7-Pad14)") (class "Default")
      (node (ref "U7") (pin "14") (pinfunction "D7_14") (pintype "bidirectional+no_connect"))
    )
    (net (code "99") (name "unconnected-(U7-D8-Pad16)") (class "Default")
      (node (ref "U7") (pin "16") (pinfunction "D8_16") (pintype "bidirectional+no_connect"))
    )
    (net (code "100") (name "unconnected-(U7-S7-Pad15)") (class "Default")
      (node (ref "U7") (pin "15") (pinfunction "S7_15") (pintype "bidirectional+no_connect"))
    )
    (net (code "101") (name "unconnected-(U7-S8-Pad17)") (class "Default")
      (node (ref "U7") (pin "17") (pinfunction "S8_17") (pintype "bidirectional+no_connect"))
    )
    (net (code "102") (name "unconnected-(U8-D7-Pad14)") (class "Default")
      (node (ref "U8") (pin "14") (pinfunction "D7_14") (pintype "bidirectional+no_connect"))
    )
    (net (code "103") (name "unconnected-(U8-D8-Pad16)") (class "Default")
      (node (ref "U8") (pin "16") (pinfunction "D8_16") (pintype "bidirectional+no_connect"))
    )
    (net (code "104") (name "unconnected-(U8-S7-Pad15)") (class "Default")
      (node (ref "U8") (pin "15") (pinfunction "S7_15") (pintype "bidirectional+no_connect"))
    )
    (net (code "105") (name "unconnected-(U8-S8-Pad17)") (class "Default")
      (node (ref "U8") (pin "17") (pinfunction "S8_17") (pintype "bidirectional+no_connect"))
    )
  )
)
